# power.net
KiCad netlist of a schematic drawn in Altium Designer
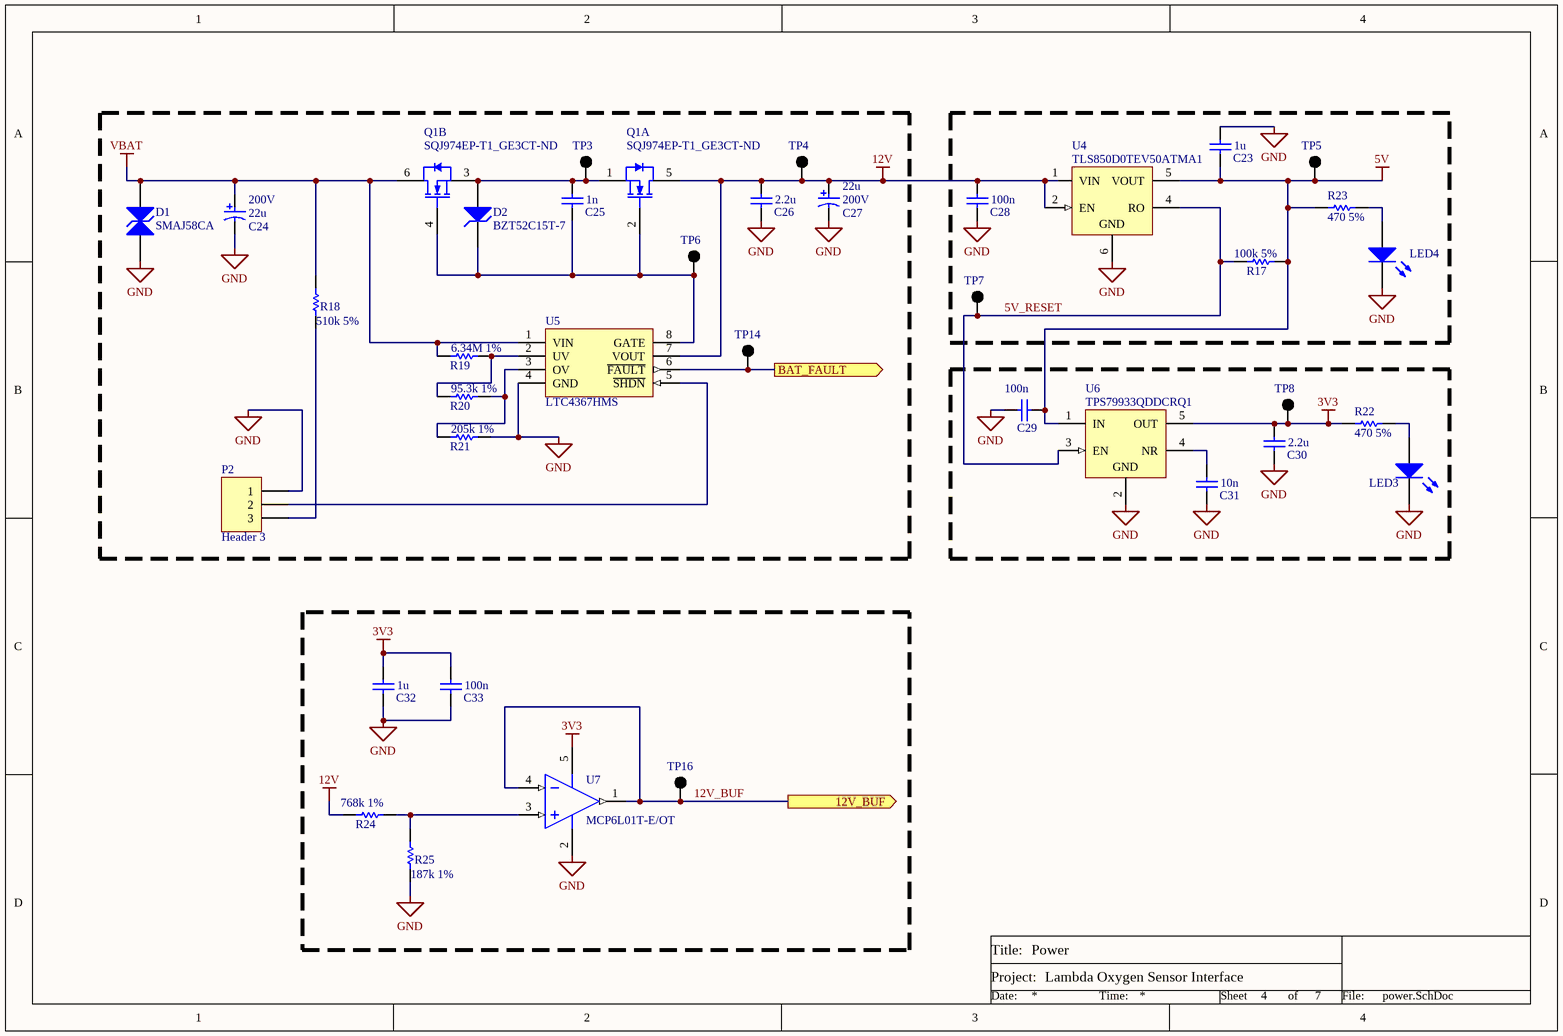
[diagram p0: power.SchDoc]

(export (version "E")
  (design (tool "Eeschema 10.0.6"))
  (components
    (comp (ref "C23")
      (value "1u")
      (footprint "1206")
      (description "Generic 1206 Capacitor")
      (libsource (lib "symbol_library") (part "C_1206"))
    )
    (comp (ref "C24")
      (value "22u")
      (footprint "NIC-UUX2A470MNL1GS_M")
      (description "Generic PCAP_10x10 Can Aluminum Electrolytic Capacitor")
      (fields (field (name "VOLTAGE") "200V") (field (name "Comment") "Generic Electrolytic Capacitor"))
      (libsource (lib "symbol_library") (part "C_can"))
    )
    (comp (ref "C25")
      (value "1n")
      (footprint "0805")
      (description "Generic 0805 Capacitor")
      (libsource (lib "symbol_library") (part "C_0805"))
    )
    (comp (ref "C26")
      (value "2.2u")
      (footprint "1206")
      (description "Generic 1206 Capacitor")
      (libsource (lib "symbol_library") (part "C_1206"))
    )
    (comp (ref "C27")
      (value "22u")
      (footprint "NIC-UUX2A470MNL1GS_M")
      (description "Generic PCAP_10x10 Can Aluminum Electrolytic Capacitor")
      (fields (field (name "VOLTAGE") "200V") (field (name "Comment") "Generic Electrolytic Capacitor"))
      (libsource (lib "symbol_library") (part "C_can"))
    )
    (comp (ref "C28")
      (value "100n")
      (footprint "0805")
      (description "Generic 0805 Capacitor")
      (libsource (lib "symbol_library") (part "C_0805"))
    )
    (comp (ref "C29")
      (value "100n")
      (footprint "0805")
      (description "Generic 0805 Capacitor")
      (libsource (lib "symbol_library") (part "C_0805"))
    )
    (comp (ref "C30")
      (value "2.2u")
      (footprint "1206")
      (description "Generic 1206 Capacitor")
      (libsource (lib "symbol_library") (part "C_1206"))
    )
    (comp (ref "C31")
      (value "10n")
      (footprint "0805")
      (description "Generic 0805 Capacitor")
      (libsource (lib "symbol_library") (part "C_0805"))
    )
    (comp (ref "C32")
      (value "1u")
      (footprint "1206")
      (description "Generic 1206 Capacitor")
      (libsource (lib "symbol_library") (part "C_1206"))
    )
    (comp (ref "C33")
      (value "100n")
      (footprint "0805")
      (description "Generic 0805 Capacitor")
      (libsource (lib "symbol_library") (part "C_0805"))
    )
    (comp (ref "D1")
      (value "SMAJ58CA")
      (footprint "VISH-DO-214AC-2_M")
      (fields
        (field (name "MANUFACTURER") "Vishay Semiconductor")
        (field (name "PARTNUMBER") "SMAJ58CA-E3/5A")
      )
      (libsource (lib "symbol_library") (part "SMAJ58CA"))
    )
    (comp (ref "D2")
      (value "BZT52C15T-7")
      (footprint "DIOD-SOD523-2_V")
      (description "Zener Diode 15V 300mW ±6% Surface Mount SOD-523")
      (fields (field (name "MANUFACTURER") "Diodes Inc") (field (name "PARTNUMBER") "BZT52C16-7-F"))
      (libsource (lib "symbol_library") (part "BZT52C15T"))
    )
    (comp (ref "LED3")
      (value "150080SS75000")
      (footprint "0805_A")
      (description "SMD mono-color Chip LED, WL-SMCW, Super Red")
      (fields (field (name "MANUFACTURER") "Wuerth Elektronik"))
      (libsource (lib "symbol_library") (part "LED_0805"))
    )
    (comp (ref "LED4")
      (value "150080SS75000")
      (footprint "0805_A")
      (description "SMD mono-color Chip LED, WL-SMCW, Super Red")
      (fields (field (name "MANUFACTURER") "Wuerth Elektronik"))
      (libsource (lib "symbol_library") (part "LED_0805"))
    )
    (comp (ref "P2")
      (value "Header 3")
      (footprint "HDR1X3")
      (description "Header, 3-Pin")
      (fields (field (name "PUBLISHER") "Altium Limited"))
      (libsource (lib "Miscellaneous Connectors") (part "Header 3"))
    )
    (comp (ref "Q1")
      (value "SQJ974EP-T1_GE3CT-ND")
      (footprint "VISH-POWERPAKSO-8_A_V")
      (description "Mosfet Array 2 N-Channel (Dual) 100V 30A (Tc) 48W Surface Mount PowerPAK® SO-8 Dual")
      (fields (field (name "MANUFACTURER") "Vishay"))
      (libsource (lib "symbol_library") (part "SQJ974EP"))
    )
    (comp (ref "R17")
      (value "100k 5%")
      (footprint "0603")
      (description "Generic 0603 Resistor")
      (libsource (lib "symbol_library") (part "R_0603"))
    )
    (comp (ref "R18")
      (value "510k 5%")
      (footprint "0603")
      (description "Generic 0603 Resistor")
      (libsource (lib "symbol_library") (part "R_0603"))
    )
    (comp (ref "R19")
      (value "6.34M 1%")
      (footprint "0603")
      (description "Generic 0603 Resistor")
      (libsource (lib "symbol_library") (part "R_0603"))
    )
    (comp (ref "R20")
      (value "95.3k 1%")
      (footprint "0603")
      (description "Generic 0603 Resistor")
      (libsource (lib "symbol_library") (part "R_0603"))
    )
    (comp (ref "R21")
      (value "205k 1%")
      (footprint "0603")
      (description "Generic 0603 Resistor")
      (libsource (lib "symbol_library") (part "R_0603"))
    )
    (comp (ref "R22")
      (value "470 5%")
      (footprint "0603")
      (description "Generic 0603 Resistor")
      (libsource (lib "symbol_library") (part "R_0603"))
    )
    (comp (ref "R23")
      (value "470 5%")
      (footprint "0603")
      (description "Generic 0603 Resistor")
      (libsource (lib "symbol_library") (part "R_0603"))
    )
    (comp (ref "R24")
      (value "768k 1%")
      (footprint "0603")
      (description "Generic 0603 Resistor")
      (libsource (lib "symbol_library") (part "R_0603"))
    )
    (comp (ref "R25")
      (value "187k 1%")
      (footprint "0603")
      (description "Generic 0603 Resistor")
      (libsource (lib "symbol_library") (part "R_0603"))
    )
    (comp (ref "TP3")
      (value "5001")
      (footprint "KSTN-5001")
      (description "Test Point, Black, 1-Pin THD, RoHS, Bulk")
      (fields (field (name "MANUFACTURER") "Keystone"))
      (libsource (lib "symbol_library") (part "TP5001"))
    )
    (comp (ref "TP4")
      (value "5001")
      (footprint "KSTN-5001")
      (description "Test Point, Black, 1-Pin THD, RoHS, Bulk")
      (fields (field (name "MANUFACTURER") "Keystone"))
      (libsource (lib "symbol_library") (part "TP5001"))
    )
    (comp (ref "TP5")
      (value "5001")
      (footprint "KSTN-5001")
      (description "Test Point, Black, 1-Pin THD, RoHS, Bulk")
      (fields (field (name "MANUFACTURER") "Keystone"))
      (libsource (lib "symbol_library") (part "TP5001"))
    )
    (comp (ref "TP6")
      (value "5001")
      (footprint "KSTN-5001")
      (description "Test Point, Black, 1-Pin THD, RoHS, Bulk")
      (fields (field (name "MANUFACTURER") "Keystone"))
      (libsource (lib "symbol_library") (part "TP5001"))
    )
    (comp (ref "TP7")
      (value "5001")
      (footprint "KSTN-5001")
      (description "Test Point, Black, 1-Pin THD, RoHS, Bulk")
      (fields (field (name "MANUFACTURER") "Keystone"))
      (libsource (lib "symbol_library") (part "TP5001"))
    )
    (comp (ref "TP8")
      (value "5001")
      (footprint "KSTN-5001")
      (description "Test Point, Black, 1-Pin THD, RoHS, Bulk")
      (fields (field (name "MANUFACTURER") "Keystone"))
      (libsource (lib "symbol_library") (part "TP5001"))
    )
    (comp (ref "TP14")
      (value "5001")
      (footprint "KSTN-5001")
      (description "Test Point, Black, 1-Pin THD, RoHS, Bulk")
      (fields (field (name "MANUFACTURER") "Keystone"))
      (libsource (lib "symbol_library") (part "TP5001"))
    )
    (comp (ref "TP16")
      (value "5001")
      (footprint "KSTN-5001")
      (description "Test Point, Black, 1-Pin THD, RoHS, Bulk")
      (fields (field (name "MANUFACTURER") "Keystone"))
      (libsource (lib "symbol_library") (part "TP5001"))
    )
    (comp (ref "U4")
      (value "TLS850D0TEV50ATMA1")
      (footprint "KVU0005A_M")
      (description "Linear Voltage Regulator IC  1 Output  500mA PG-TO252-5")
      (fields
        (field (name "PARTNUMBER") "TPS7A6150QKVURQ1")
        (field (name "MANUFACTURER") "Texas Instruments")
      )
      (libsource (lib "symbol_library") (part "TLS850D0TE"))
    )
    (comp (ref "U5")
      (value "LTC4367HMS")
      (footprint "MSOP8_M")
      (description "100V Overvoltage, Undervoltage and Reverse Supply Protection Controller")
      (libsource (lib "symbol_library") (part "LTC4367"))
    )
    (comp (ref "U6")
      (value "TPS79933QDDCRQ1")
      (footprint "DDC0005A_M")
      (fields (field (name "MANUFACTURER") "Texas Instruments"))
      (libsource (lib "symbol_library") (part "TPS79933"))
    )
    (comp (ref "U7")
      (value "MCP6L01T-E/OT")
      (footprint "DDC0005A_M")
      (description "1 MHz, 85 uA Op Amp, 5-Pin SOT-23, Extended Temperature Range")
      (libsource (lib "symbol_library") (part "MCP6L01"))
    )
  )
  (nets
    (net (code "1") (name "/5V_RESET") (class "Default")
      (node (ref "R17") (pin "1") (pinfunction "1_1") (pintype "passive"))
      (node (ref "TP7") (pin "1") (pintype "passive"))
      (node (ref "U4") (pin "4") (pinfunction "RO_4") (pintype "open_collector"))
      (node (ref "U6") (pin "3") (pinfunction "EN_3") (pintype "input"))
    )
    (net (code "2") (name "/12V_BUF") (class "Default")
      (node (ref "TP16") (pin "1") (pintype "passive"))
      (node (ref "U7") (pin "1") (pinfunction "VOUT_1") (pintype "output"))
      (node (ref "U7") (pin "4") (pinfunction "VIN-_4") (pintype "input"))
    )
    (net (code "3") (name "/BAT_FAULT") (class "Default")
      (node (ref "TP14") (pin "1") (pintype "passive"))
      (node (ref "U5") (pin "6") (pinfunction "~{FAULT}_6") (pintype "output"))
    )
    (net (code "4") (name "3V3") (class "Default")
      (node (ref "C30") (pin "2") (pinfunction "2_2") (pintype "passive"))
      (node (ref "C32") (pin "2") (pinfunction "2_2") (pintype "passive"))
      (node (ref "C33") (pin "2") (pinfunction "2_2") (pintype "passive"))
      (node (ref "R22") (pin "2") (pinfunction "2_2") (pintype "passive"))
      (node (ref "TP8") (pin "1") (pintype "passive"))
      (node (ref "U6") (pin "5") (pinfunction "OUT_5") (pintype "power_in"))
      (node (ref "U7") (pin "5") (pinfunction "VDD_5") (pintype "power_in"))
    )
    (net (code "5") (name "5V") (class "Default")
      (node (ref "C23") (pin "1") (pinfunction "1_1") (pintype "passive"))
      (node (ref "C29") (pin "2") (pinfunction "2_2") (pintype "passive"))
      (node (ref "R17") (pin "2") (pinfunction "2_2") (pintype "passive"))
      (node (ref "R23") (pin "2") (pinfunction "2_2") (pintype "passive"))
      (node (ref "TP5") (pin "1") (pintype "passive"))
      (node (ref "U4") (pin "5") (pinfunction "VOUT_5") (pintype "power_in"))
      (node (ref "U6") (pin "1") (pinfunction "IN_1") (pintype "power_in"))
    )
    (net (code "6") (name "12V") (class "Default")
      (node (ref "C26") (pin "2") (pinfunction "2_2") (pintype "passive"))
      (node (ref "C27") (pin "1") (pinfunction "1_1") (pintype "passive"))
      (node (ref "C28") (pin "2") (pinfunction "2_2") (pintype "passive"))
      (node (ref "Q1") (pin "5") (pinfunction "G2_5") (pintype "passive"))
      (node (ref "R24") (pin "1") (pinfunction "1_1") (pintype "passive"))
      (node (ref "TP4") (pin "1") (pintype "passive"))
      (node (ref "U4") (pin "1") (pinfunction "VIN_1") (pintype "power_in"))
      (node (ref "U4") (pin "2") (pinfunction "EN_2") (pintype "input"))
      (node (ref "U5") (pin "7") (pinfunction "VOUT_7") (pintype "passive"))
    )
    (net (code "7") (name "GND") (class "Default")
      (node (ref "C23") (pin "2") (pinfunction "2_2") (pintype "passive"))
      (node (ref "C24") (pin "2") (pinfunction "2_2") (pintype "passive"))
      (node (ref "C26") (pin "1") (pinfunction "1_1") (pintype "passive"))
      (node (ref "C27") (pin "2") (pinfunction "2_2") (pintype "passive"))
      (node (ref "C28") (pin "1") (pinfunction "1_1") (pintype "passive"))
      (node (ref "C29") (pin "1") (pinfunction "1_1") (pintype "passive"))
      (node (ref "C30") (pin "1") (pinfunction "1_1") (pintype "passive"))
      (node (ref "C31") (pin "1") (pinfunction "1_1") (pintype "passive"))
      (node (ref "C32") (pin "1") (pinfunction "1_1") (pintype "passive"))
      (node (ref "C33") (pin "1") (pinfunction "1_1") (pintype "passive"))
      (node (ref "D1") (pin "1") (pinfunction "A1_1") (pintype "passive"))
      (node (ref "LED3") (pin "1") (pinfunction "K_1") (pintype "passive"))
      (node (ref "LED4") (pin "1") (pinfunction "K_1") (pintype "passive"))
      (node (ref "P2") (pin "1") (pinfunction "1_1") (pintype "passive"))
      (node (ref "R21") (pin "2") (pinfunction "2_2") (pintype "passive"))
      (node (ref "R25") (pin "1") (pinfunction "1_1") (pintype "passive"))
      (node (ref "U4") (pin "6") (pinfunction "GND_6") (pintype "power_in"))
      (node (ref "U5") (pin "4") (pinfunction "GND_4") (pintype "power_in"))
      (node (ref "U6") (pin "2") (pinfunction "GND_2") (pintype "power_in"))
      (node (ref "U7") (pin "2") (pinfunction "VSS_2") (pintype "power_in"))
    )
    (net (code "8") (name "Net-(D2-A)") (class "Default")
      (node (ref "C25") (pin "2") (pinfunction "2_2") (pintype "passive"))
      (node (ref "D2") (pin "1") (pinfunction "A_1") (pintype "passive"))
      (node (ref "Q1") (pin "1") (pinfunction "S2_1") (pintype "passive"))
      (node (ref "Q1") (pin "3") (pinfunction "S2_3") (pintype "passive"))
      (node (ref "TP3") (pin "1") (pintype "passive"))
    )
    (net (code "9") (name "Net-(D2-K)") (class "Default")
      (node (ref "C25") (pin "1") (pinfunction "1_1") (pintype "passive"))
      (node (ref "D2") (pin "2") (pinfunction "K_2") (pintype "passive"))
      (node (ref "Q1") (pin "2") (pinfunction "G2_2") (pintype "passive"))
      (node (ref "Q1") (pin "4") (pinfunction "G2_4") (pintype "passive"))
      (node (ref "TP6") (pin "1") (pintype "passive"))
      (node (ref "U5") (pin "8") (pinfunction "GATE_8") (pintype "passive"))
    )
    (net (code "10") (name "Net-(LED3-A)") (class "Default")
      (node (ref "LED3") (pin "2") (pinfunction "A_2") (pintype "passive"))
      (node (ref "R22") (pin "1") (pinfunction "1_1") (pintype "passive"))
    )
    (net (code "11") (name "Net-(LED4-A)") (class "Default")
      (node (ref "LED4") (pin "2") (pinfunction "A_2") (pintype "passive"))
      (node (ref "R23") (pin "1") (pinfunction "1_1") (pintype "passive"))
    )
    (net (code "12") (name "Net-(P2-Pad3)") (class "Default")
      (node (ref "P2") (pin "3") (pinfunction "3_3") (pintype "passive"))
      (node (ref "R18") (pin "1") (pinfunction "1_1") (pintype "passive"))
    )
    (net (code "13") (name "Net-(U5-OV)") (class "Default")
      (node (ref "R20") (pin "2") (pinfunction "2_2") (pintype "passive"))
      (node (ref "R21") (pin "1") (pinfunction "1_1") (pintype "passive"))
      (node (ref "U5") (pin "3") (pinfunction "OV_3") (pintype "passive"))
    )
    (net (code "14") (name "Net-(U5-UV)") (class "Default")
      (node (ref "R19") (pin "2") (pinfunction "2_2") (pintype "passive"))
      (node (ref "R20") (pin "1") (pinfunction "1_1") (pintype "passive"))
      (node (ref "U5") (pin "2") (pinfunction "UV_2") (pintype "passive"))
    )
    (net (code "15") (name "Net-(U5-~{SHDN})") (class "Default")
      (node (ref "P2") (pin "2") (pinfunction "2_2") (pintype "passive"))
      (node (ref "U5") (pin "5") (pinfunction "~{SHDN}_5") (pintype "input"))
    )
    (net (code "16") (name "Net-(U6-NR)") (class "Default")
      (node (ref "C31") (pin "2") (pinfunction "2_2") (pintype "passive"))
      (node (ref "U6") (pin "4") (pinfunction "NR_4") (pintype "passive"))
    )
    (net (code "17") (name "Net-(U7-VIN+)") (class "Default")
      (node (ref "R24") (pin "2") (pinfunction "2_2") (pintype "passive"))
      (node (ref "R25") (pin "2") (pinfunction "2_2") (pintype "passive"))
      (node (ref "U7") (pin "3") (pinfunction "VIN+_3") (pintype "input"))
    )
    (net (code "18") (name "VBAT") (class "Default")
      (node (ref "C24") (pin "1") (pinfunction "1_1") (pintype "passive"))
      (node (ref "D1") (pin "2") (pinfunction "A2_2") (pintype "passive"))
      (node (ref "Q1") (pin "6") (pinfunction "G2_6") (pintype "passive"))
      (node (ref "R18") (pin "2") (pinfunction "2_2") (pintype "passive"))
      (node (ref "R19") (pin "1") (pinfunction "1_1") (pintype "passive"))
      (node (ref "U5") (pin "1") (pinfunction "VIN_1") (pintype "power_in"))
    )
  )
)
